# BMS_Slave_V2_0.net
KiCad netlist of a schematic drawn in EAGLE
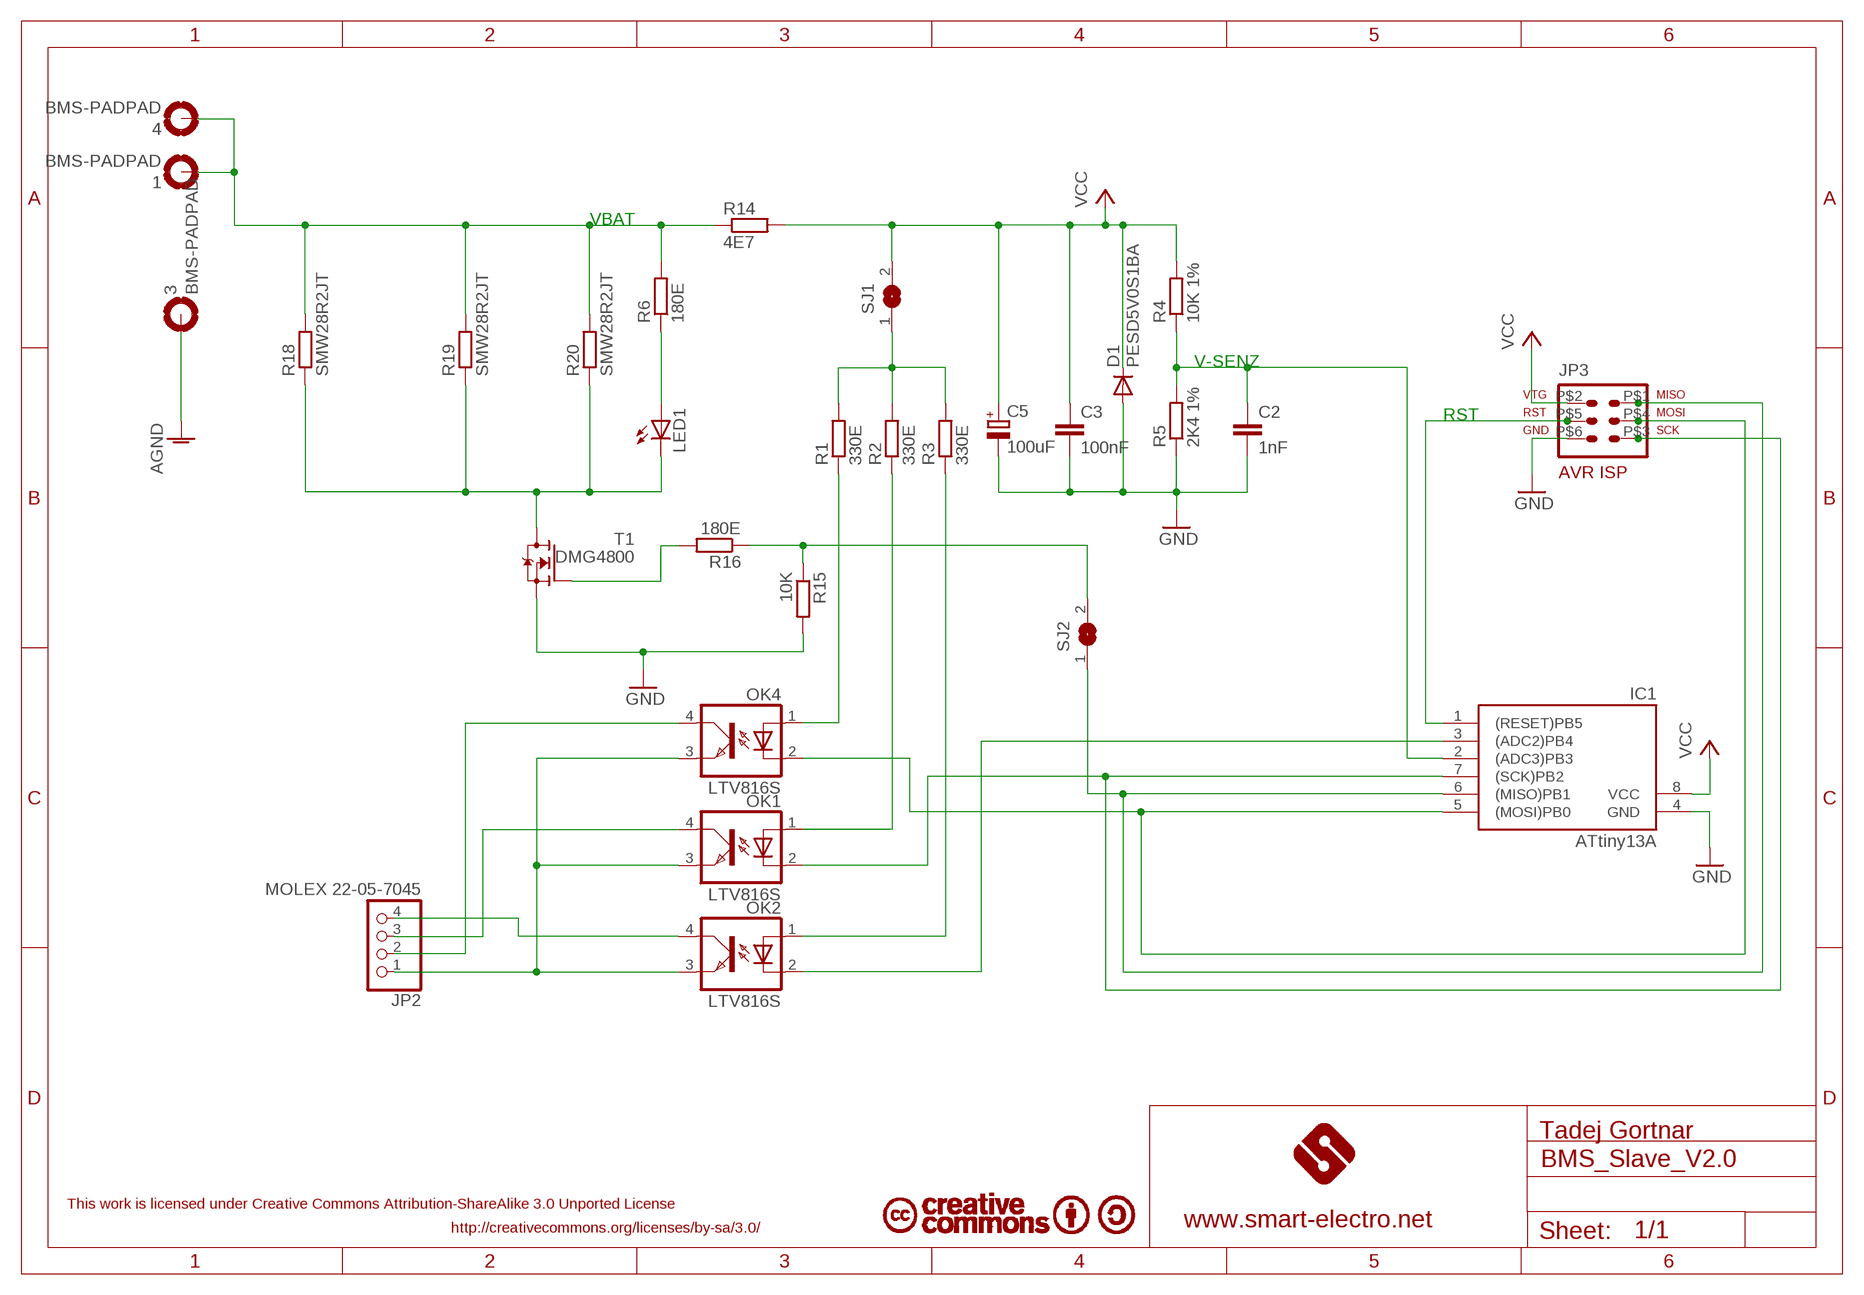
[diagram p0: schematic, sheet 1]

(export (version "E")
  (design (tool "Eeschema 10.0.6"))
  (components
    (comp (ref "1")
      (value "BMS-PADPAD")
      (footprint "eagle-import:BMSPAD")
      (libsource (lib "eagle-import") (part "BMS-PADPAD"))
    )
    (comp (ref "3")
      (value "BMS-PADPAD")
      (footprint "eagle-import:BMSPAD")
      (libsource (lib "eagle-import") (part "BMS-PADPAD"))
    )
    (comp (ref "4")
      (value "BMS-PADPAD")
      (footprint "eagle-import:BMSPAD")
      (libsource (lib "eagle-import") (part "BMS-PADPAD"))
    )
    (comp (ref "C2")
      (value "1nF")
      (footprint "eagle-import:C0805K")
      (libsource (lib "eagle-import") (part "C-EUC0805K"))
    )
    (comp (ref "C3")
      (value "100nF")
      (footprint "eagle-import:C0805K")
      (libsource (lib "eagle-import") (part "C-EUC0805K"))
    )
    (comp (ref "C5")
      (value "100uF")
      (footprint "eagle-import:153CLV-0605")
      (libsource (lib "eagle-import") (part "CPOL-EU153CLV-0605"))
    )
    (comp (ref "D1")
      (value "PESD5V0S1BA")
      (footprint "eagle-import:SOD323-W")
      (libsource (lib "eagle-import") (part "DIODE-SOD323-W"))
    )
    (comp (ref "IC1")
      (value "ATtiny13A")
      (footprint "eagle-import:SO08")
      (libsource (lib "eagle-import") (part "TINY138S2"))
    )
    (comp (ref "JP2")
      (value "MOLEX 22-05-7045")
      (footprint "eagle-import:1X04")
      (libsource (lib "eagle-import") (part "PINHD-1X4"))
    )
    (comp (ref "JP3")
      (value "AVR-ISP-6S")
      (footprint "eagle-import:6PAD_ISP_SMD")
      (libsource (lib "eagle-import") (part "AVR-ISP-6S"))
    )
    (comp (ref "LED1")
      (value "LEDCHIP-LED0805")
      (footprint "eagle-import:CHIP-LED0805")
      (libsource (lib "eagle-import") (part "LEDCHIP-LED0805"))
    )
    (comp (ref "OK1")
      (value "LTV816S")
      (footprint "eagle-import:SMD4")
      (libsource (lib "eagle-import") (part "LTV816S"))
    )
    (comp (ref "OK2")
      (value "LTV816S")
      (footprint "eagle-import:SMD4")
      (libsource (lib "eagle-import") (part "LTV816S"))
    )
    (comp (ref "OK4")
      (value "LTV816S")
      (footprint "eagle-import:SMD4")
      (libsource (lib "eagle-import") (part "LTV816S"))
    )
    (comp (ref "R1")
      (value "330E")
      (footprint "eagle-import:M0805")
      (libsource (lib "eagle-import") (part "R-EU_M0805"))
    )
    (comp (ref "R2")
      (value "330E")
      (footprint "eagle-import:M0805")
      (libsource (lib "eagle-import") (part "R-EU_M0805"))
    )
    (comp (ref "R3")
      (value "330E")
      (footprint "eagle-import:M0805")
      (libsource (lib "eagle-import") (part "R-EU_M0805"))
    )
    (comp (ref "R4")
      (value "10K 1%")
      (footprint "eagle-import:M0805")
      (libsource (lib "eagle-import") (part "R-EU_M0805"))
    )
    (comp (ref "R5")
      (value "2K4 1%")
      (footprint "eagle-import:M0805")
      (libsource (lib "eagle-import") (part "R-EU_M0805"))
    )
    (comp (ref "R6")
      (value "180E")
      (footprint "eagle-import:M0805")
      (libsource (lib "eagle-import") (part "R-EU_M0805"))
    )
    (comp (ref "R14")
      (value "4E7")
      (footprint "eagle-import:M0805")
      (libsource (lib "eagle-import") (part "R-EU_M0805"))
    )
    (comp (ref "R15")
      (value "10K")
      (footprint "eagle-import:M0805")
      (libsource (lib "eagle-import") (part "R-EU_M0805"))
    )
    (comp (ref "R16")
      (value "180E")
      (footprint "eagle-import:M0805")
      (libsource (lib "eagle-import") (part "R-EU_M0805"))
    )
    (comp (ref "R18")
      (value "SMW28R2JT")
      (footprint "eagle-import:R2512W")
      (libsource (lib "eagle-import") (part "resistor_R-EU_R2512W"))
    )
    (comp (ref "R19")
      (value "SMW28R2JT")
      (footprint "eagle-import:R2512W")
      (libsource (lib "eagle-import") (part "resistor_R-EU_R2512W"))
    )
    (comp (ref "R20")
      (value "SMW28R2JT")
      (footprint "eagle-import:R2512W")
      (libsource (lib "eagle-import") (part "resistor_R-EU_R2512W"))
    )
    (comp (ref "SJ1") (value "SJ") (footprint "eagle-import:SJ") (libsource (lib "eagle-import") (part "SJ")))
    (comp (ref "SJ2") (value "SJ") (footprint "eagle-import:SJ") (libsource (lib "eagle-import") (part "SJ")))
    (comp (ref "T1")
      (value "DMG4800")
      (footprint "eagle-import:TO252")
      (libsource (lib "eagle-import") (part "DMG4800"))
    )
  )
  (nets
    (net (code "1") (name "/RST") (class "Default")
      (node (ref "IC1") (pin "1") (pinfunction "(RESET)PB5_1") (pintype "bidirectional"))
      (node (ref "JP3") (pin "P$5") (pinfunction "5_P$5") (pintype "passive"))
    )
    (net (code "2") (name "/V-SENZ") (class "Default")
      (node (ref "C2") (pin "1") (pinfunction "1_1") (pintype "passive"))
      (node (ref "IC1") (pin "2") (pinfunction "(ADC3)PB3_2") (pintype "bidirectional"))
      (node (ref "R4") (pin "1") (pinfunction "1_1") (pintype "passive"))
      (node (ref "R5") (pin "2") (pinfunction "2_2") (pintype "passive"))
    )
    (net (code "3") (name "/VBAT") (class "Default")
      (node (ref "1") (pin "B5,5") (pinfunction "MOUNT_B5,5") (pintype "passive"))
      (node (ref "4") (pin "B5,5") (pinfunction "MOUNT_B5,5") (pintype "passive"))
      (node (ref "R14") (pin "1") (pinfunction "1_1") (pintype "passive"))
      (node (ref "R18") (pin "2") (pinfunction "2_2") (pintype "passive"))
      (node (ref "R19") (pin "2") (pinfunction "2_2") (pintype "passive"))
      (node (ref "R20") (pin "2") (pinfunction "2_2") (pintype "passive"))
      (node (ref "R6") (pin "2") (pinfunction "2_2") (pintype "passive"))
    )
    (net (code "4") (name "AGND") (class "Default")
      (node (ref "3") (pin "B5,5") (pinfunction "MOUNT_B5,5") (pintype "passive"))
    )
    (net (code "5") (name "GND") (class "Default")
      (node (ref "C2") (pin "2") (pinfunction "2_2") (pintype "passive"))
      (node (ref "C3") (pin "2") (pinfunction "2_2") (pintype "passive"))
      (node (ref "C5") (pin "-") (pinfunction "-_-") (pintype "passive"))
      (node (ref "D1") (pin "A") (pinfunction "A_A") (pintype "passive"))
      (node (ref "IC1") (pin "4") (pinfunction "GND_4") (pintype "power_in"))
      (node (ref "JP3") (pin "P$6") (pinfunction "6_P$6") (pintype "passive"))
      (node (ref "R15") (pin "2") (pinfunction "2_2") (pintype "passive"))
      (node (ref "R5") (pin "1") (pinfunction "1_1") (pintype "passive"))
      (node (ref "T1") (pin "2") (pinfunction "S_2") (pintype "passive"))
    )
    (net (code "6") (name "Net-(IC1-(ADC2)PB4)") (class "Default")
      (node (ref "IC1") (pin "3") (pinfunction "(ADC2)PB4_3") (pintype "bidirectional"))
      (node (ref "OK2") (pin "2") (pinfunction "C_2") (pintype "passive"))
    )
    (net (code "7") (name "Net-(IC1-(MISO)PB1)") (class "Default")
      (node (ref "IC1") (pin "6") (pinfunction "(MISO)PB1_6") (pintype "bidirectional"))
      (node (ref "JP3") (pin "P$1") (pinfunction "1_P$1") (pintype "passive"))
      (node (ref "SJ2") (pin "1") (pinfunction "1_1") (pintype "passive"))
    )
    (net (code "8") (name "Net-(IC1-(MOSI)PB0)") (class "Default")
      (node (ref "IC1") (pin "5") (pinfunction "(MOSI)PB0_5") (pintype "bidirectional"))
      (node (ref "JP3") (pin "P$4") (pinfunction "4_P$4") (pintype "passive"))
      (node (ref "OK4") (pin "2") (pinfunction "C_2") (pintype "passive"))
    )
    (net (code "9") (name "Net-(IC1-(SCK)PB2)") (class "Default")
      (node (ref "IC1") (pin "7") (pinfunction "(SCK)PB2_7") (pintype "bidirectional"))
      (node (ref "JP3") (pin "P$3") (pinfunction "3_P$3") (pintype "passive"))
      (node (ref "OK1") (pin "2") (pinfunction "C_2") (pintype "passive"))
    )
    (net (code "10") (name "Net-(LED1-PadA)") (class "Default")
      (node (ref "LED1") (pin "A") (pinfunction "A_A") (pintype "passive"))
      (node (ref "R6") (pin "1") (pinfunction "1_1") (pintype "passive"))
    )
    (net (code "11") (name "Net-(OK1-A)") (class "Default")
      (node (ref "OK1") (pin "1") (pinfunction "A_1") (pintype "passive"))
      (node (ref "R2") (pin "1") (pinfunction "1_1") (pintype "passive"))
    )
    (net (code "12") (name "Net-(OK1-COL)") (class "Default")
      (node (ref "JP2") (pin "3") (pinfunction "3_3") (pintype "passive"))
      (node (ref "OK1") (pin "4") (pinfunction "COL_4") (pintype "passive"))
    )
    (net (code "13") (name "Net-(OK1-EMIT)") (class "Default")
      (node (ref "JP2") (pin "1") (pinfunction "1_1") (pintype "passive"))
      (node (ref "OK1") (pin "3") (pinfunction "EMIT_3") (pintype "passive"))
      (node (ref "OK2") (pin "3") (pinfunction "EMIT_3") (pintype "passive"))
      (node (ref "OK4") (pin "3") (pinfunction "EMIT_3") (pintype "passive"))
    )
    (net (code "14") (name "Net-(OK2-A)") (class "Default")
      (node (ref "OK2") (pin "1") (pinfunction "A_1") (pintype "passive"))
      (node (ref "R3") (pin "1") (pinfunction "1_1") (pintype "passive"))
    )
    (net (code "15") (name "Net-(OK2-COL)") (class "Default")
      (node (ref "JP2") (pin "4") (pinfunction "4_4") (pintype "passive"))
      (node (ref "OK2") (pin "4") (pinfunction "COL_4") (pintype "passive"))
    )
    (net (code "16") (name "Net-(OK4-A)") (class "Default")
      (node (ref "OK4") (pin "1") (pinfunction "A_1") (pintype "passive"))
      (node (ref "R1") (pin "1") (pinfunction "1_1") (pintype "passive"))
    )
    (net (code "17") (name "Net-(OK4-COL)") (class "Default")
      (node (ref "JP2") (pin "2") (pinfunction "2_2") (pintype "passive"))
      (node (ref "OK4") (pin "4") (pinfunction "COL_4") (pintype "passive"))
    )
    (net (code "18") (name "Net-(R1-Pad2)") (class "Default")
      (node (ref "R1") (pin "2") (pinfunction "2_2") (pintype "passive"))
      (node (ref "R2") (pin "2") (pinfunction "2_2") (pintype "passive"))
      (node (ref "R3") (pin "2") (pinfunction "2_2") (pintype "passive"))
      (node (ref "SJ1") (pin "1") (pinfunction "1_1") (pintype "passive"))
    )
    (net (code "19") (name "Net-(R15-Pad1)") (class "Default")
      (node (ref "R15") (pin "1") (pinfunction "1_1") (pintype "passive"))
      (node (ref "R16") (pin "1") (pinfunction "1_1") (pintype "passive"))
      (node (ref "SJ2") (pin "2") (pinfunction "2_2") (pintype "passive"))
    )
    (net (code "20") (name "Net-(T1-D)") (class "Default")
      (node (ref "LED1") (pin "C") (pinfunction "C_C") (pintype "passive"))
      (node (ref "R18") (pin "1") (pinfunction "1_1") (pintype "passive"))
      (node (ref "R19") (pin "1") (pinfunction "1_1") (pintype "passive"))
      (node (ref "R20") (pin "1") (pinfunction "1_1") (pintype "passive"))
      (node (ref "T1") (pin "3") (pinfunction "D_3") (pintype "passive"))
    )
    (net (code "21") (name "Net-(T1-G)") (class "Default")
      (node (ref "R16") (pin "2") (pinfunction "2_2") (pintype "passive"))
      (node (ref "T1") (pin "1") (pinfunction "G_1") (pintype "passive"))
    )
    (net (code "22") (name "VCC") (class "Default")
      (node (ref "C3") (pin "1") (pinfunction "1_1") (pintype "passive"))
      (node (ref "C5") (pin "+") (pinfunction "+_+") (pintype "passive"))
      (node (ref "D1") (pin "C") (pinfunction "C_C") (pintype "passive"))
      (node (ref "IC1") (pin "8") (pinfunction "VCC_8") (pintype "power_in"))
      (node (ref "JP3") (pin "P$2") (pinfunction "2_P$2") (pintype "passive"))
      (node (ref "R14") (pin "2") (pinfunction "2_2") (pintype "passive"))
      (node (ref "R4") (pin "2") (pinfunction "2_2") (pintype "passive"))
      (node (ref "SJ1") (pin "2") (pinfunction "2_2") (pintype "passive"))
    )
  )
)
